# SCH_BQ25798-test-board-mppt-solar_2026-0.net
KiCad netlist of a schematic drawn in EasyEDA
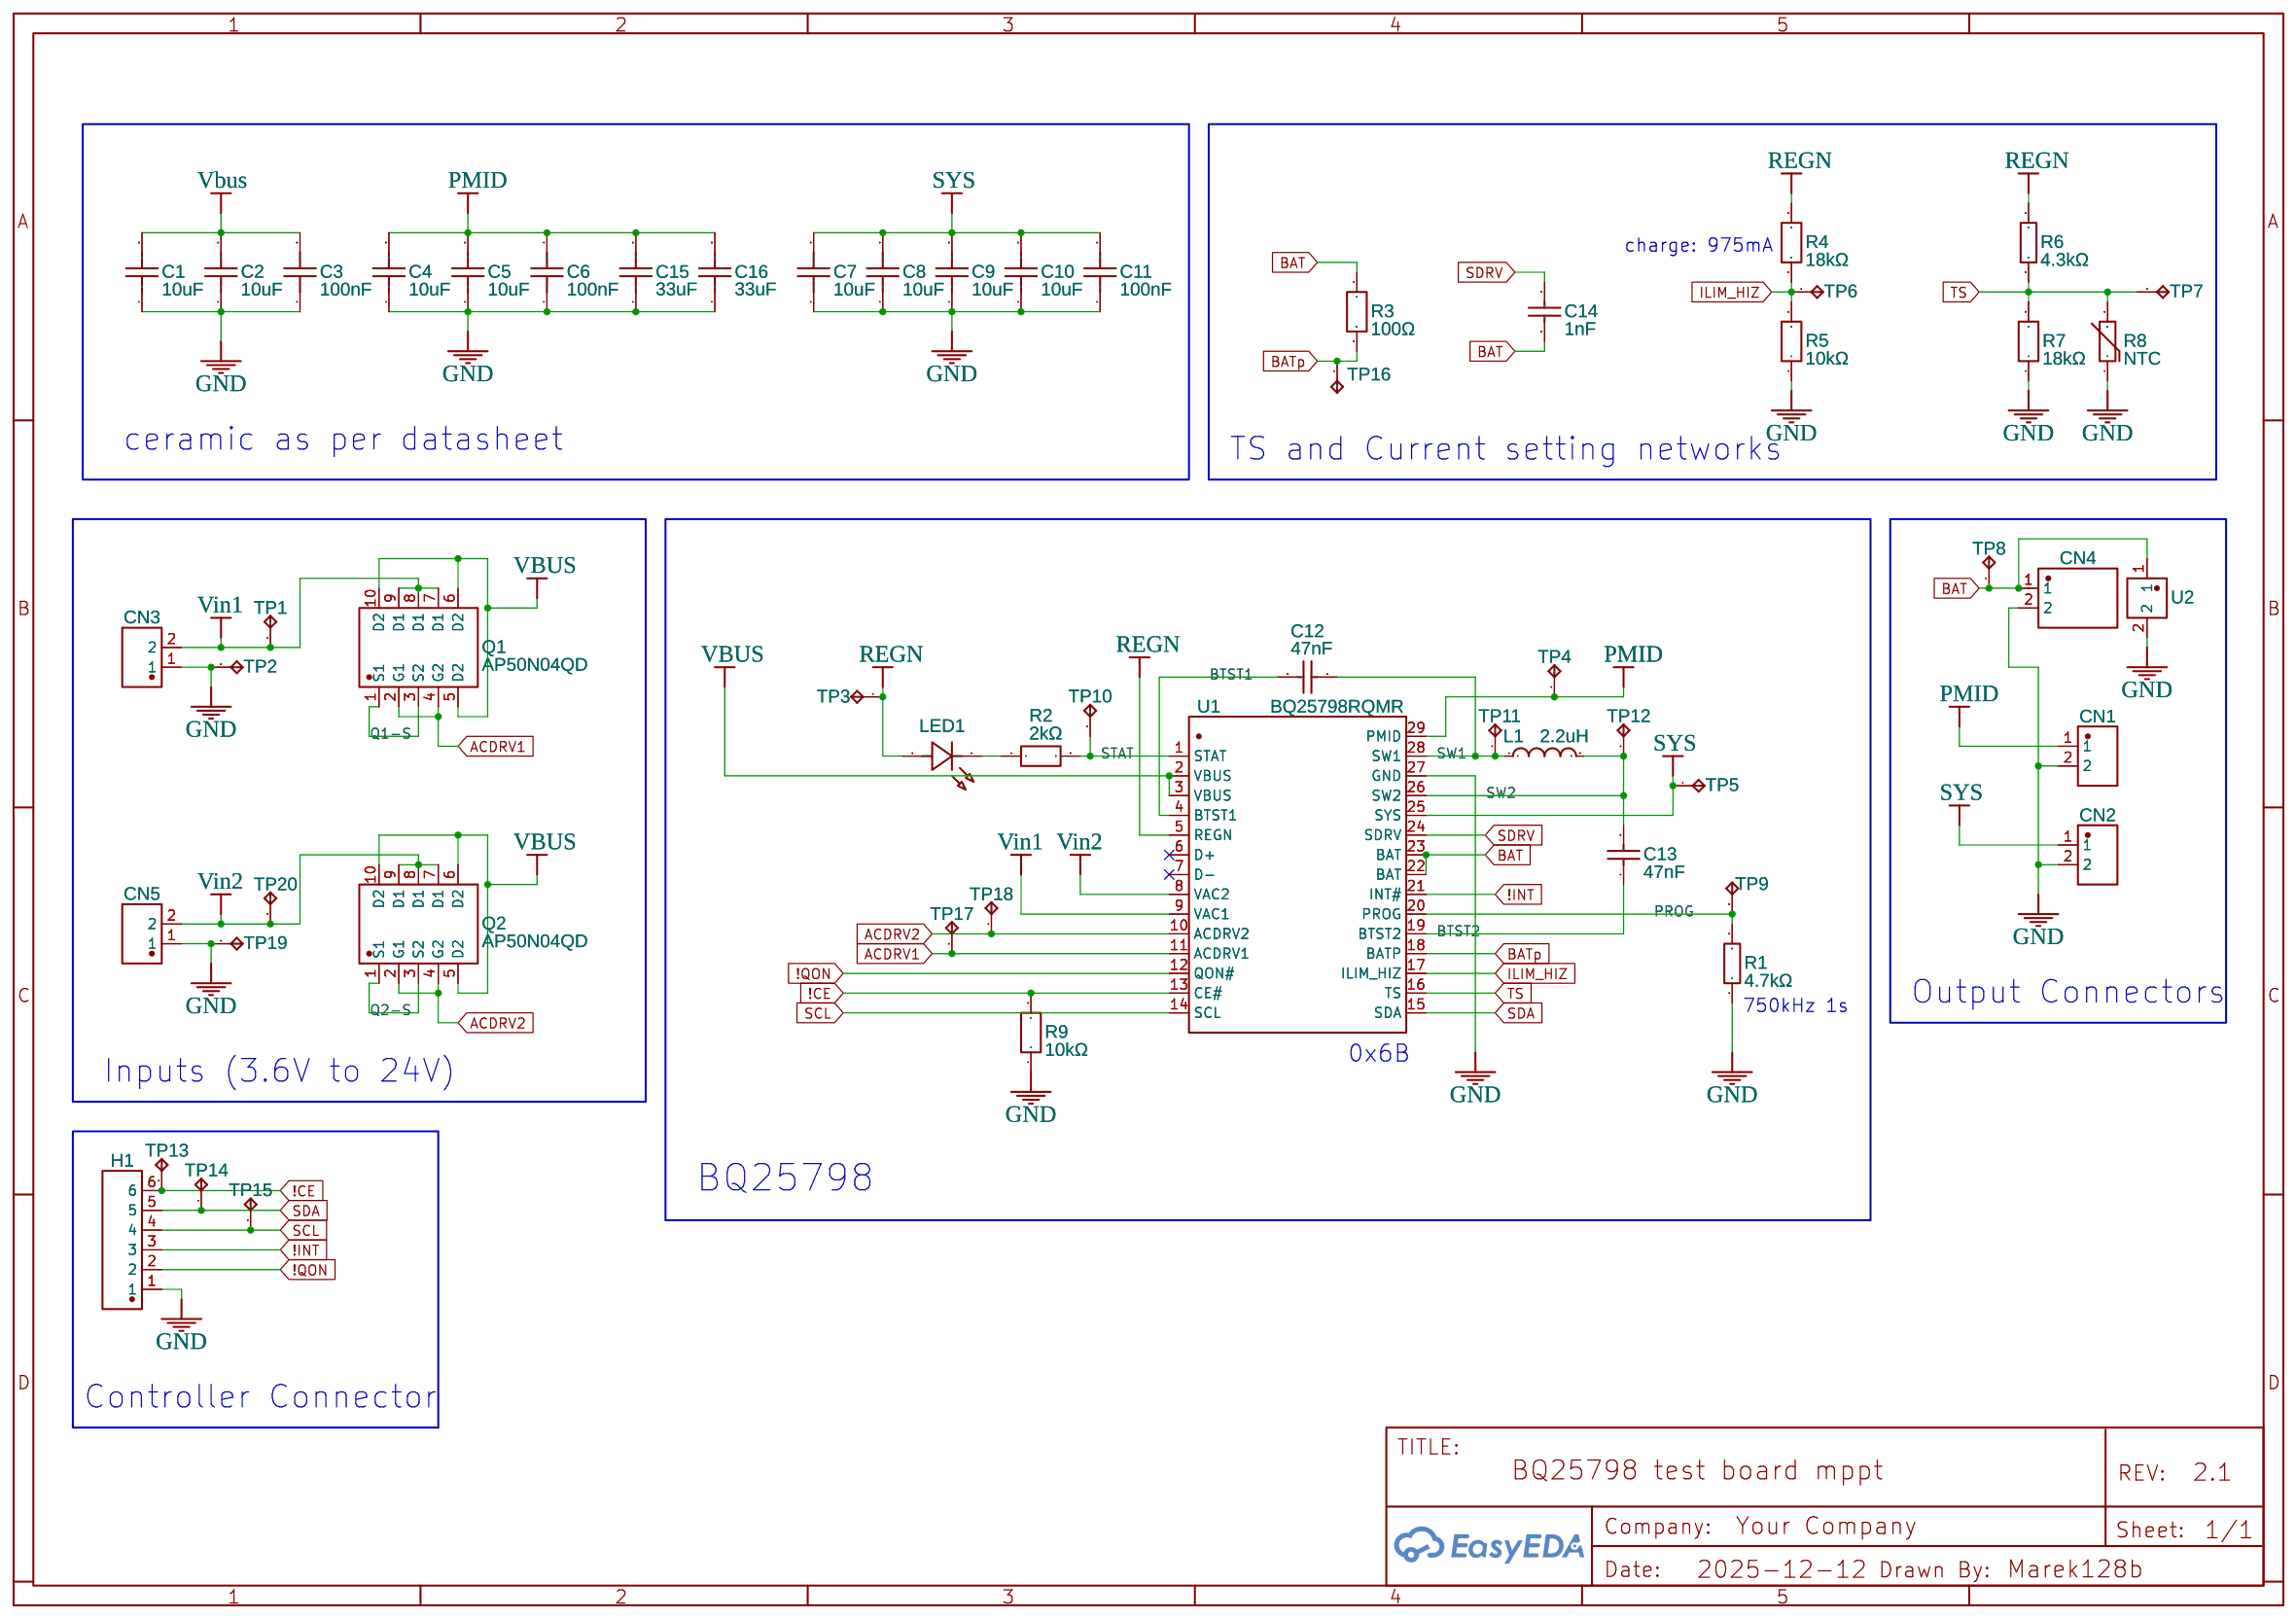
[diagram p0: schematic sheet]

(export (version "E")
  (design (tool "Eeschema 10.0.6"))
  (components
    (comp (ref "C1")
      (value "10uF")
      (fields
        (field (name "Manufacturer Part") "CL21A106KAYNNNE")
        (field (name "Manufacturer") "SAMSUNG(三星)")
      )
      (libsource (lib "") (part "CL21A106KAYNNNE"))
    )
    (comp (ref "C2")
      (value "10uF")
      (fields
        (field (name "Manufacturer Part") "CL21A106KAYNNNE")
        (field (name "Manufacturer") "SAMSUNG(三星)")
      )
      (libsource (lib "") (part "CL21A106KAYNNNE"))
    )
    (comp (ref "C3")
      (value "100nF")
      (fields
        (field (name "Manufacturer Part") "CC0603KRX7R9BB104")
        (field (name "Manufacturer") "YAGEO(国巨)")
      )
      (libsource (lib "") (part "CC0603KRX7R9BB104"))
    )
    (comp (ref "C4")
      (value "10uF")
      (fields
        (field (name "Manufacturer Part") "CL21A106KAYNNNE")
        (field (name "Manufacturer") "SAMSUNG(三星)")
      )
      (libsource (lib "") (part "CL21A106KAYNNNE"))
    )
    (comp (ref "C5")
      (value "10uF")
      (fields
        (field (name "Manufacturer Part") "CL21A106KAYNNNE")
        (field (name "Manufacturer") "SAMSUNG(三星)")
      )
      (libsource (lib "") (part "CL21A106KAYNNNE"))
    )
    (comp (ref "C6")
      (value "100nF")
      (fields
        (field (name "Manufacturer Part") "CC0603KRX7R9BB104")
        (field (name "Manufacturer") "YAGEO(国巨)")
      )
      (libsource (lib "") (part "CC0603KRX7R9BB104"))
    )
    (comp (ref "C7")
      (value "10uF")
      (fields
        (field (name "Manufacturer Part") "CL21A106KAYNNNE")
        (field (name "Manufacturer") "SAMSUNG(三星)")
      )
      (libsource (lib "") (part "CL21A106KAYNNNE"))
    )
    (comp (ref "C8")
      (value "10uF")
      (fields
        (field (name "Manufacturer Part") "CL21A106KAYNNNE")
        (field (name "Manufacturer") "SAMSUNG(三星)")
      )
      (libsource (lib "") (part "CL21A106KAYNNNE"))
    )
    (comp (ref "C9")
      (value "10uF")
      (fields
        (field (name "Manufacturer Part") "CL21A106KAYNNNE")
        (field (name "Manufacturer") "SAMSUNG(三星)")
      )
      (libsource (lib "") (part "CL21A106KAYNNNE"))
    )
    (comp (ref "C10")
      (value "10uF")
      (fields
        (field (name "Manufacturer Part") "CL21A106KAYNNNE")
        (field (name "Manufacturer") "SAMSUNG(三星)")
      )
      (libsource (lib "") (part "CL21A106KAYNNNE"))
    )
    (comp (ref "C11")
      (value "100nF")
      (fields
        (field (name "Manufacturer Part") "CC0603KRX7R9BB104")
        (field (name "Manufacturer") "YAGEO(国巨)")
      )
      (libsource (lib "") (part "CC0603KRX7R9BB104"))
    )
    (comp (ref "C12")
      (value "47nF")
      (fields
        (field (name "Manufacturer Part") "CC0603KRX7R9BB473")
        (field (name "Manufacturer") "YAGEO(国巨)")
      )
      (libsource (lib "") (part "CC0603KRX7R9BB473_1"))
    )
    (comp (ref "C13")
      (value "47nF")
      (fields
        (field (name "Manufacturer Part") "CC0603KRX7R9BB473")
        (field (name "Manufacturer") "YAGEO(国巨)")
      )
      (libsource (lib "") (part "CC0603KRX7R9BB473"))
    )
    (comp (ref "C14")
      (value "1nF")
      (fields
        (field (name "Manufacturer Part") "CC0603KRX7R9BB102")
        (field (name "Manufacturer") "YAGEO(国巨)")
      )
      (libsource (lib "") (part "CC0603KRX7R9BB102"))
    )
    (comp (ref "C15")
      (value "33uF")
      (fields (field (name "Manufacturer Part") "C3216X5R1E336MT000E") (field (name "Manufacturer") "TDK"))
      (libsource (lib "") (part "C3216X5R1E336MT000E"))
    )
    (comp (ref "C16")
      (value "33uF")
      (fields (field (name "Manufacturer Part") "C3216X5R1E336MT000E") (field (name "Manufacturer") "TDK"))
      (libsource (lib "") (part "C3216X5R1E336MT000E"))
    )
    (comp (ref "CN1")
      (value "MX126-5.0-GN01-02P-CU-S-A")
      (fields
        (field (name "Manufacturer Part") "MX126-5.0-02P-GN01-Cu-S-A")
        (field (name "Manufacturer") "MAX(迈旭)")
      )
      (libsource (lib "") (part "MX126-5.0-GN01-02P-CU-S-A_1"))
    )
    (comp (ref "CN2")
      (value "MX126-5.0-GN01-02P-CU-S-A")
      (fields
        (field (name "Manufacturer Part") "MX126-5.0-02P-GN01-Cu-S-A")
        (field (name "Manufacturer") "MAX(迈旭)")
      )
      (libsource (lib "") (part "MX126-5.0-GN01-02P-CU-S-A_1"))
    )
    (comp (ref "CN3")
      (value "MX126-5.0-GN01-02P-CU-S-A")
      (fields
        (field (name "Manufacturer Part") "MX126-5.0-02P-GN01-Cu-S-A")
        (field (name "Manufacturer") "MAX(迈旭)")
      )
      (libsource (lib "") (part "MX126-5.0-GN01-02P-CU-S-A"))
    )
    (comp (ref "CN4")
      (value "B2B-XH-A (LF)(SN)")
      (fields (field (name "Manufacturer Part") "B2B-XH-A(LF)(SN)") (field (name "Manufacturer") "JST"))
      (libsource (lib "") (part "B2B-XH-A (LF)(SN)"))
    )
    (comp (ref "CN5")
      (value "MX126-5.0-GN01-02P-CU-S-A")
      (fields
        (field (name "Manufacturer Part") "MX126-5.0-02P-GN01-Cu-S-A")
        (field (name "Manufacturer") "MAX(迈旭)")
      )
      (libsource (lib "") (part "MX126-5.0-GN01-02P-CU-S-A"))
    )
    (comp (ref "H1")
      (value "HB-PH3-25416PB2GOP")
      (fields (field (name "Manufacturer") "HANBO(汉博)"))
      (libsource (lib "") (part "HB-PH3-25416PB2GOP"))
    )
    (comp (ref "L1")
      (value "2.2uH")
      (fields (field (name "Manufacturer Part") "APH0630T2R2M") (field (name "Manufacturer") "APV(爱普微)"))
      (libsource (lib "") (part "APH0630T2R2M"))
    )
    (comp (ref "LED1")
      (value "XL-2012UBC")
      (fields (field (name "Manufacturer") "XINGLIGHT(成兴光)"))
      (libsource (lib "") (part "XL-2012UBC"))
    )
    (comp (ref "Q1")
      (value "AP50N04QD")
      (fields (field (name "Manufacturer") "ALLPOWER(铨力)"))
      (libsource (lib "") (part "AP50N04QD"))
    )
    (comp (ref "Q2")
      (value "AP50N04QD")
      (fields (field (name "Manufacturer") "ALLPOWER(铨力)"))
      (libsource (lib "") (part "AP50N04QD"))
    )
    (comp (ref "R1")
      (value "4.7kΩ")
      (fields (field (name "Manufacturer Part") "RC0805FR-074K7L") (field (name "Manufacturer") "YAGEO(国巨)"))
      (libsource (lib "") (part "RC0805FR-074K7L"))
    )
    (comp (ref "R2")
      (value "2kΩ")
      (fields (field (name "Manufacturer Part") "FRC0805F2001TS") (field (name "Manufacturer") "FOJAN(富捷)"))
      (libsource (lib "") (part "FRC0805F2001TS"))
    )
    (comp (ref "R3")
      (value "100Ω")
      (fields (field (name "Manufacturer Part") "FRC0805J101 TS") (field (name "Manufacturer") "FOJAN(富捷)"))
      (libsource (lib "") (part "FRC0805J101 TS"))
    )
    (comp (ref "R4")
      (value "18kΩ")
      (fields (field (name "Manufacturer Part") "FRC0805F1802TS") (field (name "Manufacturer") "FOJAN(富捷)"))
      (libsource (lib "") (part "FRC0805F1802TS"))
    )
    (comp (ref "R5")
      (value "10kΩ")
      (fields (field (name "Manufacturer Part") "FRC0805J103TS") (field (name "Manufacturer") "FOJAN(富捷)"))
      (libsource (lib "") (part "FRC0805J103TS"))
    )
    (comp (ref "R6")
      (value "4.3kΩ")
      (fields
        (field (name "Manufacturer Part") "0805W8F4301T5E")
        (field (name "Manufacturer") "UNI-ROYAL(厚声)")
      )
      (libsource (lib "") (part "0805W8F4301T5E"))
    )
    (comp (ref "R7")
      (value "18kΩ")
      (fields (field (name "Manufacturer Part") "FRC0805F1802TS") (field (name "Manufacturer") "FOJAN(富捷)"))
      (libsource (lib "") (part "FRC0805F1802TS"))
    )
    (comp (ref "R8")
      (value "NTC")
      (fields (field (name "Manufacturer Part") "CMFB103F3950FANT") (field (name "Manufacturer") "FH(风华)"))
      (libsource (lib "") (part "CMFB103F3950FANT"))
    )
    (comp (ref "R9")
      (value "10kΩ")
      (fields (field (name "Manufacturer Part") "FRC0805J103TS") (field (name "Manufacturer") "FOJAN(富捷)"))
      (libsource (lib "") (part "FRC0805J103TS"))
    )
    (comp (ref "TP1") (value "TP") (libsource (lib "") (part "TP_1")))
    (comp (ref "TP2") (value "TP") (libsource (lib "") (part "TP")))
    (comp (ref "TP3") (value "TP") (libsource (lib "") (part "TP_2")))
    (comp (ref "TP4") (value "TP") (libsource (lib "") (part "TP_1")))
    (comp (ref "TP5") (value "TP") (libsource (lib "") (part "TP")))
    (comp (ref "TP6") (value "TP") (libsource (lib "") (part "TP")))
    (comp (ref "TP7") (value "TP") (libsource (lib "") (part "TP")))
    (comp (ref "TP8") (value "TP") (libsource (lib "") (part "TP_1")))
    (comp (ref "TP9") (value "TP") (libsource (lib "") (part "TP_1")))
    (comp (ref "TP10") (value "TP") (libsource (lib "") (part "TP_1")))
    (comp (ref "TP11") (value "TP") (libsource (lib "") (part "TP_1")))
    (comp (ref "TP12") (value "TP") (libsource (lib "") (part "TP_1")))
    (comp (ref "TP13") (value "TP") (libsource (lib "") (part "TP_1")))
    (comp (ref "TP14") (value "TP") (libsource (lib "") (part "TP_1")))
    (comp (ref "TP15") (value "TP") (libsource (lib "") (part "TP_1")))
    (comp (ref "TP16") (value "TP") (libsource (lib "") (part "TP_3")))
    (comp (ref "TP17") (value "TP") (libsource (lib "") (part "TP_1")))
    (comp (ref "TP18") (value "TP") (libsource (lib "") (part "TP_1")))
    (comp (ref "TP19") (value "TP") (libsource (lib "") (part "TP")))
    (comp (ref "TP20") (value "TP") (libsource (lib "") (part "TP_1")))
    (comp (ref "U1")
      (value "BQ25798RQMR")
      (fields (field (name "Manufacturer") "TI(德州仪器)"))
      (libsource (lib "") (part "BQ25798RQMR"))
    )
    (comp (ref "U2")
      (value "XT60PB-M.G.Y")
      (fields (field (name "Manufacturer") "AMASS(艾迈斯)"))
      (libsource (lib "") (part "XT60PB-M.G.Y"))
    )
  )
  (nets
    (net (code "1") (name "!CE") (class "Default")
      (node (ref "H1") (pin "6") (pinfunction "6_6") (pintype "unspecified"))
      (node (ref "R9") (pin "2") (pinfunction "2_2") (pintype "unspecified"))
      (node (ref "TP13") (pin "1") (pinfunction "1_1") (pintype "unspecified"))
      (node (ref "U1") (pin "13") (pinfunction "CE#_13") (pintype "unspecified"))
    )
    (net (code "2") (name "!INT") (class "Default")
      (node (ref "H1") (pin "3") (pinfunction "3_3") (pintype "unspecified"))
      (node (ref "U1") (pin "21") (pinfunction "INT#_21") (pintype "unspecified"))
    )
    (net (code "3") (name "!QON") (class "Default")
      (node (ref "H1") (pin "2") (pinfunction "2_2") (pintype "unspecified"))
      (node (ref "U1") (pin "12") (pinfunction "QON#_12") (pintype "unspecified"))
    )
    (net (code "4") (name "/BTST1") (class "Default")
      (node (ref "C12") (pin "2") (pinfunction "2_2") (pintype "input"))
      (node (ref "U1") (pin "4") (pinfunction "BTST1_4") (pintype "unspecified"))
    )
    (net (code "5") (name "/BTST2") (class "Default")
      (node (ref "C13") (pin "1") (pinfunction "1_1") (pintype "input"))
      (node (ref "U1") (pin "19") (pinfunction "BTST2_19") (pintype "unspecified"))
    )
    (net (code "6") (name "/PROG") (class "Default")
      (node (ref "R1") (pin "2") (pinfunction "2_2") (pintype "input"))
      (node (ref "TP9") (pin "1") (pinfunction "1_1") (pintype "unspecified"))
      (node (ref "U1") (pin "20") (pinfunction "PROG_20") (pintype "unspecified"))
    )
    (net (code "7") (name "/Q1-S") (class "Default")
      (node (ref "Q1") (pin "1") (pinfunction "S1_1") (pintype "unspecified"))
      (node (ref "Q1") (pin "3") (pinfunction "S2_3") (pintype "unspecified"))
    )
    (net (code "8") (name "/Q2-S") (class "Default")
      (node (ref "Q2") (pin "1") (pinfunction "S1_1") (pintype "unspecified"))
      (node (ref "Q2") (pin "3") (pinfunction "S2_3") (pintype "unspecified"))
    )
    (net (code "9") (name "/STAT") (class "Default")
      (node (ref "R2") (pin "2") (pinfunction "2_2") (pintype "unspecified"))
      (node (ref "TP10") (pin "1") (pinfunction "1_1") (pintype "unspecified"))
      (node (ref "U1") (pin "1") (pinfunction "STAT_1") (pintype "unspecified"))
    )
    (net (code "10") (name "/SW1") (class "Default")
      (node (ref "C12") (pin "1") (pinfunction "1_1") (pintype "input"))
      (node (ref "L1") (pin "1") (pinfunction "1_1") (pintype "unspecified"))
      (node (ref "TP11") (pin "1") (pinfunction "1_1") (pintype "unspecified"))
      (node (ref "U1") (pin "28") (pinfunction "SW1_28") (pintype "unspecified"))
    )
    (net (code "11") (name "/SW2") (class "Default")
      (node (ref "C13") (pin "2") (pinfunction "2_2") (pintype "input"))
      (node (ref "L1") (pin "2") (pinfunction "2_2") (pintype "unspecified"))
      (node (ref "TP12") (pin "1") (pinfunction "1_1") (pintype "unspecified"))
      (node (ref "U1") (pin "26") (pinfunction "SW2_26") (pintype "unspecified"))
    )
    (net (code "12") (name "ACDRV1") (class "Default")
      (node (ref "Q1") (pin "2") (pinfunction "G1_2") (pintype "unspecified"))
      (node (ref "Q1") (pin "4") (pinfunction "G2_4") (pintype "unspecified"))
      (node (ref "TP17") (pin "1") (pinfunction "1_1") (pintype "unspecified"))
      (node (ref "U1") (pin "11") (pinfunction "ACDRV1_11") (pintype "unspecified"))
    )
    (net (code "13") (name "ACDRV2") (class "Default")
      (node (ref "Q2") (pin "2") (pinfunction "G1_2") (pintype "unspecified"))
      (node (ref "Q2") (pin "4") (pinfunction "G2_4") (pintype "unspecified"))
      (node (ref "TP18") (pin "1") (pinfunction "1_1") (pintype "unspecified"))
      (node (ref "U1") (pin "10") (pinfunction "ACDRV2_10") (pintype "unspecified"))
    )
    (net (code "14") (name "BAT") (class "Default")
      (node (ref "C14") (pin "1") (pinfunction "1_1") (pintype "input"))
      (node (ref "CN4") (pin "1") (pinfunction "1_1") (pintype "unspecified"))
      (node (ref "R3") (pin "1") (pinfunction "1_1") (pintype "unspecified"))
      (node (ref "TP8") (pin "1") (pinfunction "1_1") (pintype "unspecified"))
      (node (ref "U1") (pin "22") (pinfunction "BAT_22") (pintype "unspecified"))
      (node (ref "U1") (pin "23") (pinfunction "BAT_23") (pintype "unspecified"))
      (node (ref "U2") (pin "1") (pinfunction "1_1") (pintype "unspecified"))
    )
    (net (code "15") (name "BATp") (class "Default")
      (node (ref "R3") (pin "2") (pinfunction "2_2") (pintype "unspecified"))
      (node (ref "TP16") (pin "1") (pinfunction "1_1") (pintype "unspecified"))
      (node (ref "U1") (pin "18") (pinfunction "BATP_18") (pintype "unspecified"))
    )
    (net (code "16") (name "GND") (class "Default")
      (node (ref "C1") (pin "1") (pinfunction "1_1") (pintype "unspecified"))
      (node (ref "C10") (pin "1") (pinfunction "1_1") (pintype "unspecified"))
      (node (ref "C11") (pin "1") (pinfunction "1_1") (pintype "unspecified"))
      (node (ref "C15") (pin "1") (pinfunction "1_1") (pintype "unspecified"))
      (node (ref "C16") (pin "1") (pinfunction "1_1") (pintype "unspecified"))
      (node (ref "C2") (pin "1") (pinfunction "1_1") (pintype "unspecified"))
      (node (ref "C3") (pin "1") (pinfunction "1_1") (pintype "unspecified"))
      (node (ref "C4") (pin "1") (pinfunction "1_1") (pintype "unspecified"))
      (node (ref "C5") (pin "1") (pinfunction "1_1") (pintype "unspecified"))
      (node (ref "C6") (pin "1") (pinfunction "1_1") (pintype "unspecified"))
      (node (ref "C7") (pin "1") (pinfunction "1_1") (pintype "unspecified"))
      (node (ref "C8") (pin "1") (pinfunction "1_1") (pintype "unspecified"))
      (node (ref "C9") (pin "1") (pinfunction "1_1") (pintype "unspecified"))
      (node (ref "CN1") (pin "2") (pinfunction "2_2") (pintype "unspecified"))
      (node (ref "CN2") (pin "2") (pinfunction "2_2") (pintype "unspecified"))
      (node (ref "CN3") (pin "1") (pinfunction "1_1") (pintype "unspecified"))
      (node (ref "CN4") (pin "2") (pinfunction "2_2") (pintype "unspecified"))
      (node (ref "CN5") (pin "1") (pinfunction "1_1") (pintype "unspecified"))
      (node (ref "H1") (pin "1") (pinfunction "1_1") (pintype "unspecified"))
      (node (ref "R1") (pin "1") (pinfunction "1_1") (pintype "input"))
      (node (ref "R5") (pin "1") (pinfunction "1_1") (pintype "unspecified"))
      (node (ref "R7") (pin "1") (pinfunction "1_1") (pintype "unspecified"))
      (node (ref "R8") (pin "1") (pinfunction "1_1") (pintype "input"))
      (node (ref "R9") (pin "1") (pinfunction "1_1") (pintype "unspecified"))
      (node (ref "TP19") (pin "1") (pinfunction "1_1") (pintype "unspecified"))
      (node (ref "TP2") (pin "1") (pinfunction "1_1") (pintype "unspecified"))
      (node (ref "U1") (pin "27") (pinfunction "GND_27") (pintype "unspecified"))
      (node (ref "U2") (pin "2") (pinfunction "2_2") (pintype "unspecified"))
    )
    (net (code "17") (name "ILIM_HIZ") (class "Default")
      (node (ref "R4") (pin "1") (pinfunction "1_1") (pintype "unspecified"))
      (node (ref "R5") (pin "2") (pinfunction "2_2") (pintype "unspecified"))
      (node (ref "TP6") (pin "1") (pinfunction "1_1") (pintype "unspecified"))
      (node (ref "U1") (pin "17") (pinfunction "ILIM_HIZ_17") (pintype "unspecified"))
    )
    (net (code "18") (name "Net-(LED1-K)") (class "Default")
      (node (ref "LED1") (pin "1") (pinfunction "K_1") (pintype "unspecified"))
      (node (ref "R2") (pin "1") (pinfunction "1_1") (pintype "unspecified"))
    )
    (net (code "19") (name "PMID") (class "Default")
      (node (ref "C15") (pin "2") (pinfunction "2_2") (pintype "unspecified"))
      (node (ref "C16") (pin "2") (pinfunction "2_2") (pintype "unspecified"))
      (node (ref "C4") (pin "2") (pinfunction "2_2") (pintype "unspecified"))
      (node (ref "C5") (pin "2") (pinfunction "2_2") (pintype "unspecified"))
      (node (ref "C6") (pin "2") (pinfunction "2_2") (pintype "unspecified"))
      (node (ref "CN1") (pin "1") (pinfunction "1_1") (pintype "unspecified"))
      (node (ref "TP4") (pin "1") (pinfunction "1_1") (pintype "unspecified"))
      (node (ref "U1") (pin "29") (pinfunction "PMID_29") (pintype "unspecified"))
    )
    (net (code "20") (name "REGN") (class "Default")
      (node (ref "LED1") (pin "2") (pinfunction "A_2") (pintype "unspecified"))
      (node (ref "R4") (pin "2") (pinfunction "2_2") (pintype "unspecified"))
      (node (ref "R6") (pin "2") (pinfunction "2_2") (pintype "input"))
      (node (ref "TP3") (pin "1") (pinfunction "1_1") (pintype "unspecified"))
      (node (ref "U1") (pin "5") (pinfunction "REGN_5") (pintype "unspecified"))
    )
    (net (code "21") (name "SCL") (class "Default")
      (node (ref "H1") (pin "4") (pinfunction "4_4") (pintype "unspecified"))
      (node (ref "TP15") (pin "1") (pinfunction "1_1") (pintype "unspecified"))
      (node (ref "U1") (pin "14") (pinfunction "SCL_14") (pintype "unspecified"))
    )
    (net (code "22") (name "SDA") (class "Default")
      (node (ref "H1") (pin "5") (pinfunction "5_5") (pintype "unspecified"))
      (node (ref "TP14") (pin "1") (pinfunction "1_1") (pintype "unspecified"))
      (node (ref "U1") (pin "15") (pinfunction "SDA_15") (pintype "unspecified"))
    )
    (net (code "23") (name "SDRV") (class "Default")
      (node (ref "C14") (pin "2") (pinfunction "2_2") (pintype "input"))
      (node (ref "U1") (pin "24") (pinfunction "SDRV_24") (pintype "unspecified"))
    )
    (net (code "24") (name "SYS") (class "Default")
      (node (ref "C10") (pin "2") (pinfunction "2_2") (pintype "unspecified"))
      (node (ref "C11") (pin "2") (pinfunction "2_2") (pintype "unspecified"))
      (node (ref "C7") (pin "2") (pinfunction "2_2") (pintype "unspecified"))
      (node (ref "C8") (pin "2") (pinfunction "2_2") (pintype "unspecified"))
      (node (ref "C9") (pin "2") (pinfunction "2_2") (pintype "unspecified"))
      (node (ref "CN2") (pin "1") (pinfunction "1_1") (pintype "unspecified"))
      (node (ref "TP5") (pin "1") (pinfunction "1_1") (pintype "unspecified"))
      (node (ref "U1") (pin "25") (pinfunction "SYS_25") (pintype "unspecified"))
    )
    (net (code "25") (name "TS") (class "Default")
      (node (ref "R6") (pin "1") (pinfunction "1_1") (pintype "input"))
      (node (ref "R7") (pin "2") (pinfunction "2_2") (pintype "unspecified"))
      (node (ref "R8") (pin "2") (pinfunction "2_2") (pintype "input"))
      (node (ref "TP7") (pin "1") (pinfunction "1_1") (pintype "unspecified"))
      (node (ref "U1") (pin "16") (pinfunction "TS_16") (pintype "unspecified"))
    )
    (net (code "26") (name "VBUS") (class "Default")
      (node (ref "Q1") (pin "10") (pinfunction "D2_10") (pintype "unspecified"))
      (node (ref "Q1") (pin "5") (pinfunction "D2_5") (pintype "unspecified"))
      (node (ref "Q1") (pin "6") (pinfunction "D2_6") (pintype "unspecified"))
      (node (ref "Q2") (pin "10") (pinfunction "D2_10") (pintype "unspecified"))
      (node (ref "Q2") (pin "5") (pinfunction "D2_5") (pintype "unspecified"))
      (node (ref "Q2") (pin "6") (pinfunction "D2_6") (pintype "unspecified"))
      (node (ref "U1") (pin "2") (pinfunction "VBUS_2") (pintype "unspecified"))
      (node (ref "U1") (pin "3") (pinfunction "VBUS_3") (pintype "unspecified"))
    )
    (net (code "27") (name "Vbus") (class "Default")
      (node (ref "C1") (pin "2") (pinfunction "2_2") (pintype "unspecified"))
      (node (ref "C2") (pin "2") (pinfunction "2_2") (pintype "unspecified"))
      (node (ref "C3") (pin "2") (pinfunction "2_2") (pintype "unspecified"))
    )
    (net (code "28") (name "Vin1") (class "Default")
      (node (ref "CN3") (pin "2") (pinfunction "2_2") (pintype "unspecified"))
      (node (ref "Q1") (pin "7") (pinfunction "D1_7") (pintype "unspecified"))
      (node (ref "Q1") (pin "8") (pinfunction "D1_8") (pintype "unspecified"))
      (node (ref "Q1") (pin "9") (pinfunction "D1_9") (pintype "unspecified"))
      (node (ref "TP1") (pin "1") (pinfunction "1_1") (pintype "unspecified"))
      (node (ref "U1") (pin "9") (pinfunction "VAC1_9") (pintype "unspecified"))
    )
    (net (code "29") (name "Vin2") (class "Default")
      (node (ref "CN5") (pin "2") (pinfunction "2_2") (pintype "unspecified"))
      (node (ref "Q2") (pin "7") (pinfunction "D1_7") (pintype "unspecified"))
      (node (ref "Q2") (pin "8") (pinfunction "D1_8") (pintype "unspecified"))
      (node (ref "Q2") (pin "9") (pinfunction "D1_9") (pintype "unspecified"))
      (node (ref "TP20") (pin "1") (pinfunction "1_1") (pintype "unspecified"))
      (node (ref "U1") (pin "8") (pinfunction "VAC2_8") (pintype "unspecified"))
    )
    (net (code "30") (name "unconnected-(U1-D+-Pad6)") (class "Default")
      (node (ref "U1") (pin "6") (pinfunction "D+_6") (pintype "unspecified+no_connect"))
    )
    (net (code "31") (name "unconnected-(U1-D--Pad7)") (class "Default")
      (node (ref "U1") (pin "7") (pinfunction "D-_7") (pintype "unspecified+no_connect"))
    )
  )
)
